# DSP_GPIO_Digital.net
KiCad netlist of a schematic drawn in Altium Designer
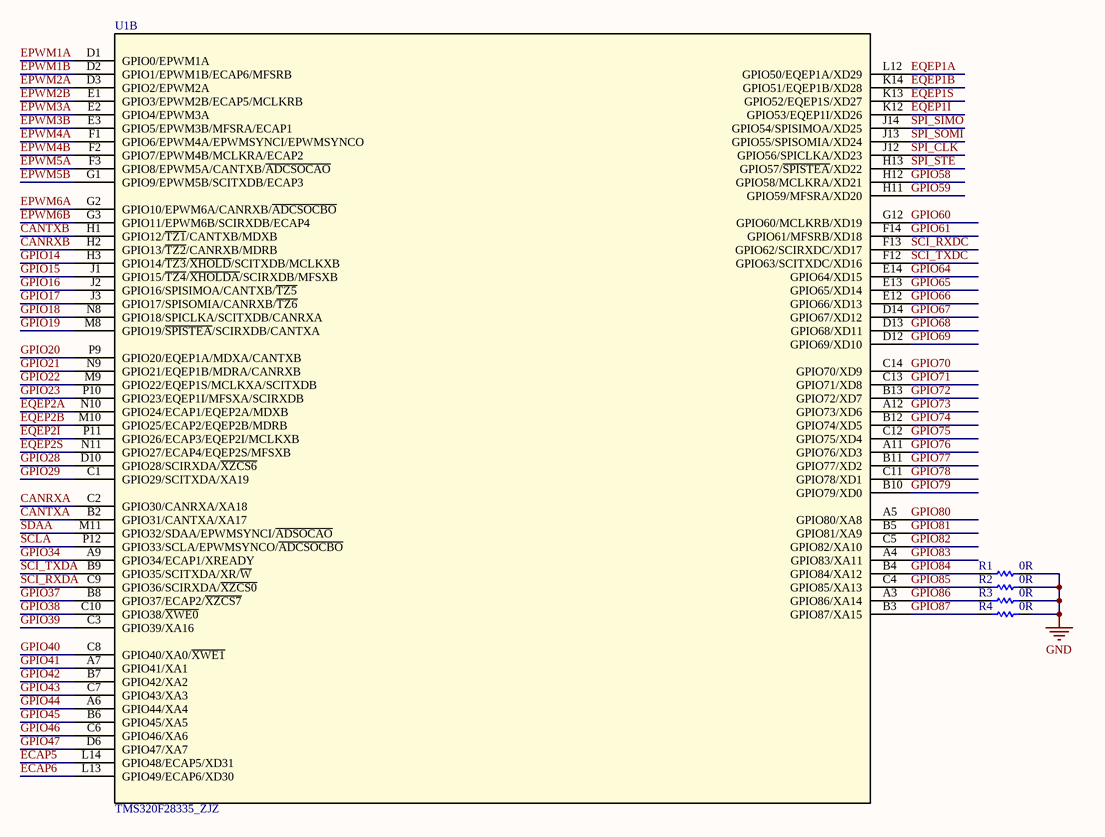
[diagram p0: DSP_GPIO&Digital.SchDoc]

(export (version "E")
  (design (tool "Eeschema 10.0.6"))
  (components
    (comp (ref "R1")
      (value "0R")
      (footprint "r0603")
      (description "Resistor")
      (fields (field (name "Comment") "Res1") (field (name "PUBLISHER") "Altium Limited"))
      (libsource (lib "Miscellaneous Devices") (part "Res1"))
    )
    (comp (ref "R2")
      (value "0R")
      (footprint "r0603")
      (description "Resistor")
      (fields (field (name "Comment") "Res1") (field (name "PUBLISHER") "Altium Limited"))
      (libsource (lib "Miscellaneous Devices") (part "Res1"))
    )
    (comp (ref "R3")
      (value "0R")
      (footprint "r0603")
      (description "Resistor")
      (fields (field (name "Comment") "Res1") (field (name "PUBLISHER") "Altium Limited"))
      (libsource (lib "Miscellaneous Devices") (part "Res1"))
    )
    (comp (ref "R4")
      (value "0R")
      (footprint "r0603")
      (description "Resistor")
      (fields (field (name "Comment") "Res1") (field (name "PUBLISHER") "Altium Limited"))
      (libsource (lib "Miscellaneous Devices") (part "Res1"))
    )
    (comp (ref "U1")
      (value "TMS320F28335_ZJZ")
      (footprint "ZJZ176")
      (description "Imported")
      (fields
        (field (name "MANUFACTURER") "Texas Instruments")
        (field (name "GENERIC_PART_NUMBER") "TMS320F28335")
      )
      (libsource (lib "schlib_by_wjy") (part "TMS320F28335_ZJZ"))
    )
  )
  (nets
    (net (code "1") (name "/CANRXA") (class "Default")
      (node (ref "U1") (pin "C2") (pinfunction "GPIO30/CANRXA/XA18_C2") (pintype "passive"))
    )
    (net (code "2") (name "/CANRXB") (class "Default")
      (node (ref "U1") (pin "H2") (pinfunction "GPIO13/~{TZ2}/CANRXB/MDRB_H2") (pintype "passive"))
    )
    (net (code "3") (name "/CANTXA") (class "Default")
      (node (ref "U1") (pin "B2") (pinfunction "GPIO31/CANTXA/XA17_B2") (pintype "passive"))
    )
    (net (code "4") (name "/CANTXB") (class "Default")
      (node (ref "U1") (pin "H1") (pinfunction "GPIO12/~{TZ1}/CANTXB/MDXB_H1") (pintype "passive"))
    )
    (net (code "5") (name "/ECAP5") (class "Default")
      (node (ref "U1") (pin "L14") (pinfunction "GPIO48/ECAP5/XD31_L14") (pintype "passive"))
    )
    (net (code "6") (name "/ECAP6") (class "Default")
      (node (ref "U1") (pin "L13") (pinfunction "GPIO49/ECAP6/XD30_L13") (pintype "passive"))
    )
    (net (code "7") (name "/EPWM1A") (class "Default")
      (node (ref "U1") (pin "D1") (pinfunction "GPIO0/EPWM1A_D1") (pintype "passive"))
    )
    (net (code "8") (name "/EPWM1B") (class "Default")
      (node (ref "U1") (pin "D2") (pinfunction "GPIO1/EPWM1B/ECAP6/MFSRB_D2") (pintype "passive"))
    )
    (net (code "9") (name "/EPWM2A") (class "Default")
      (node (ref "U1") (pin "D3") (pinfunction "GPIO2/EPWM2A_D3") (pintype "passive"))
    )
    (net (code "10") (name "/EPWM2B") (class "Default")
      (node (ref "U1") (pin "E1") (pinfunction "GPIO3/EPWM2B/ECAP5/MCLKRB_E1") (pintype "passive"))
    )
    (net (code "11") (name "/EPWM3A") (class "Default")
      (node (ref "U1") (pin "E2") (pinfunction "GPIO4/EPWM3A_E2") (pintype "passive"))
    )
    (net (code "12") (name "/EPWM3B") (class "Default")
      (node (ref "U1") (pin "E3") (pinfunction "GPIO5/EPWM3B/MFSRA/ECAP1_E3") (pintype "passive"))
    )
    (net (code "13") (name "/EPWM4A") (class "Default")
      (node (ref "U1") (pin "F1") (pinfunction "GPIO6/EPWM4A/EPWMSYNCI/EPWMSYNCO_F1") (pintype "passive"))
    )
    (net (code "14") (name "/EPWM4B") (class "Default")
      (node (ref "U1") (pin "F2") (pinfunction "GPIO7/EPWM4B/MCLKRA/ECAP2_F2") (pintype "passive"))
    )
    (net (code "15") (name "/EPWM5A") (class "Default")
      (node (ref "U1") (pin "F3") (pinfunction "GPIO8/EPWM5A/CANTXB/~{ADCSOCAO}_F3") (pintype "passive"))
    )
    (net (code "16") (name "/EPWM5B") (class "Default")
      (node (ref "U1") (pin "G1") (pinfunction "GPIO9/EPWM5B/SCITXDB/ECAP3_G1") (pintype "passive"))
    )
    (net (code "17") (name "/EPWM6A") (class "Default")
      (node (ref "U1") (pin "G2") (pinfunction "GPIO10/EPWM6A/CANRXB/~{ADCSOCBO}_G2") (pintype "passive"))
    )
    (net (code "18") (name "/EPWM6B") (class "Default")
      (node (ref "U1") (pin "G3") (pinfunction "GPIO11/EPWM6B/SCIRXDB/ECAP4_G3") (pintype "passive"))
    )
    (net (code "19") (name "/EQEP1A") (class "Default")
      (node (ref "U1") (pin "L12") (pinfunction "GPIO50/EQEP1A/XD29_L12") (pintype "passive"))
    )
    (net (code "20") (name "/EQEP1B") (class "Default")
      (node (ref "U1") (pin "K14") (pinfunction "GPIO51/EQEP1B/XD28_K14") (pintype "passive"))
    )
    (net (code "21") (name "/EQEP1I") (class "Default")
      (node (ref "U1") (pin "K12") (pinfunction "GPIO53/EQEP1I/XD26_K12") (pintype "passive"))
    )
    (net (code "22") (name "/EQEP1S") (class "Default")
      (node (ref "U1") (pin "K13") (pinfunction "GPIO52/EQEP1S/XD27_K13") (pintype "passive"))
    )
    (net (code "23") (name "/EQEP2A") (class "Default")
      (node (ref "U1") (pin "N10") (pinfunction "GPIO24/ECAP1/EQEP2A/MDXB_N10") (pintype "passive"))
    )
    (net (code "24") (name "/EQEP2B") (class "Default")
      (node (ref "U1") (pin "M10") (pinfunction "GPIO25/ECAP2/EQEP2B/MDRB_M10") (pintype "passive"))
    )
    (net (code "25") (name "/EQEP2I") (class "Default")
      (node (ref "U1") (pin "P11") (pinfunction "GPIO26/ECAP3/EQEP2I/MCLKXB_P11") (pintype "passive"))
    )
    (net (code "26") (name "/EQEP2S") (class "Default")
      (node (ref "U1") (pin "N11") (pinfunction "GPIO27/ECAP4/EQEP2S/MFSXB_N11") (pintype "passive"))
    )
    (net (code "27") (name "/GPIO14") (class "Default")
      (node (ref "U1") (pin "H3") (pinfunction "GPIO14/~{TZ3}/~{XHOLD}/SCITXDB/MCLKXB_H3") (pintype "passive"))
    )
    (net (code "28") (name "/GPIO15") (class "Default")
      (node (ref "U1") (pin "J1") (pinfunction "GPIO15/~{TZ4}/~{XHOLDA}/SCIRXDB/MFSXB_J1") (pintype "passive"))
    )
    (net (code "29") (name "/GPIO16") (class "Default")
      (node (ref "U1") (pin "J2") (pinfunction "GPIO16/SPISIMOA/CANTXB/~{TZ5}_J2") (pintype "passive"))
    )
    (net (code "30") (name "/GPIO17") (class "Default")
      (node (ref "U1") (pin "J3") (pinfunction "GPIO17/SPISOMIA/CANRXB/~{TZ6}_J3") (pintype "passive"))
    )
    (net (code "31") (name "/GPIO18") (class "Default")
      (node (ref "U1") (pin "N8") (pinfunction "GPIO18/SPICLKA/SCITXDB/CANRXA_N8") (pintype "passive"))
    )
    (net (code "32") (name "/GPIO19") (class "Default")
      (node (ref "U1") (pin "M8") (pinfunction "GPIO19/~{SPISTEA}/SCIRXDB/CANTXA_M8") (pintype "passive"))
    )
    (net (code "33") (name "/GPIO20") (class "Default")
      (node (ref "U1") (pin "P9") (pinfunction "GPIO20/EQEP1A/MDXA/CANTXB_P9") (pintype "passive"))
    )
    (net (code "34") (name "/GPIO21") (class "Default")
      (node (ref "U1") (pin "N9") (pinfunction "GPIO21/EQEP1B/MDRA/CANRXB_N9") (pintype "passive"))
    )
    (net (code "35") (name "/GPIO22") (class "Default")
      (node (ref "U1") (pin "M9") (pinfunction "GPIO22/EQEP1S/MCLKXA/SCITXDB_M9") (pintype "passive"))
    )
    (net (code "36") (name "/GPIO23") (class "Default")
      (node (ref "U1") (pin "P10") (pinfunction "GPIO23/EQEP1I/MFSXA/SCIRXDB_P10") (pintype "passive"))
    )
    (net (code "37") (name "/GPIO28") (class "Default")
      (node (ref "U1") (pin "D10") (pinfunction "GPIO28/SCIRXDA/~{XZCS6}_D10") (pintype "passive"))
    )
    (net (code "38") (name "/GPIO29") (class "Default")
      (node (ref "U1") (pin "C1") (pinfunction "GPIO29/SCITXDA/XA19_C1") (pintype "passive"))
    )
    (net (code "39") (name "/GPIO34") (class "Default")
      (node (ref "U1") (pin "A9") (pinfunction "GPIO34/ECAP1/XREADY_A9") (pintype "passive"))
    )
    (net (code "40") (name "/GPIO37") (class "Default")
      (node (ref "U1") (pin "B8") (pinfunction "GPIO37/ECAP2/~{XZCS7}_B8") (pintype "passive"))
    )
    (net (code "41") (name "/GPIO38") (class "Default")
      (node (ref "U1") (pin "C10") (pinfunction "GPIO38/~{XWE0}_C10") (pintype "passive"))
    )
    (net (code "42") (name "/GPIO39") (class "Default")
      (node (ref "U1") (pin "C3") (pinfunction "GPIO39/XA16_C3") (pintype "passive"))
    )
    (net (code "43") (name "/GPIO40") (class "Default")
      (node (ref "U1") (pin "C8") (pinfunction "GPIO40/XA0/~{XWE1}_C8") (pintype "passive"))
    )
    (net (code "44") (name "/GPIO41") (class "Default")
      (node (ref "U1") (pin "A7") (pinfunction "GPIO41/XA1_A7") (pintype "passive"))
    )
    (net (code "45") (name "/GPIO42") (class "Default")
      (node (ref "U1") (pin "B7") (pinfunction "GPIO42/XA2_B7") (pintype "passive"))
    )
    (net (code "46") (name "/GPIO43") (class "Default")
      (node (ref "U1") (pin "C7") (pinfunction "GPIO43/XA3_C7") (pintype "passive"))
    )
    (net (code "47") (name "/GPIO44") (class "Default")
      (node (ref "U1") (pin "A6") (pinfunction "GPIO44/XA4_A6") (pintype "passive"))
    )
    (net (code "48") (name "/GPIO45") (class "Default")
      (node (ref "U1") (pin "B6") (pinfunction "GPIO45/XA5_B6") (pintype "passive"))
    )
    (net (code "49") (name "/GPIO46") (class "Default")
      (node (ref "U1") (pin "C6") (pinfunction "GPIO46/XA6_C6") (pintype "passive"))
    )
    (net (code "50") (name "/GPIO47") (class "Default")
      (node (ref "U1") (pin "D6") (pinfunction "GPIO47/XA7_D6") (pintype "passive"))
    )
    (net (code "51") (name "/GPIO58") (class "Default")
      (node (ref "U1") (pin "H12") (pinfunction "GPIO58/MCLKRA/XD21_H12") (pintype "passive"))
    )
    (net (code "52") (name "/GPIO59") (class "Default")
      (node (ref "U1") (pin "H11") (pinfunction "GPIO59/MFSRA/XD20_H11") (pintype "passive"))
    )
    (net (code "53") (name "/GPIO60") (class "Default")
      (node (ref "U1") (pin "G12") (pinfunction "GPIO60/MCLKRB/XD19_G12") (pintype "passive"))
    )
    (net (code "54") (name "/GPIO61") (class "Default")
      (node (ref "U1") (pin "F14") (pinfunction "GPIO61/MFSRB/XD18_F14") (pintype "passive"))
    )
    (net (code "55") (name "/GPIO64") (class "Default")
      (node (ref "U1") (pin "E14") (pinfunction "GPIO64/XD15_E14") (pintype "passive"))
    )
    (net (code "56") (name "/GPIO65") (class "Default")
      (node (ref "U1") (pin "E13") (pinfunction "GPIO65/XD14_E13") (pintype "passive"))
    )
    (net (code "57") (name "/GPIO66") (class "Default")
      (node (ref "U1") (pin "E12") (pinfunction "GPIO66/XD13_E12") (pintype "passive"))
    )
    (net (code "58") (name "/GPIO67") (class "Default")
      (node (ref "U1") (pin "D14") (pinfunction "GPIO67/XD12_D14") (pintype "passive"))
    )
    (net (code "59") (name "/GPIO68") (class "Default")
      (node (ref "U1") (pin "D13") (pinfunction "GPIO68/XD11_D13") (pintype "passive"))
    )
    (net (code "60") (name "/GPIO69") (class "Default")
      (node (ref "U1") (pin "D12") (pinfunction "GPIO69/XD10_D12") (pintype "passive"))
    )
    (net (code "61") (name "/GPIO70") (class "Default")
      (node (ref "U1") (pin "C14") (pinfunction "GPIO70/XD9_C14") (pintype "passive"))
    )
    (net (code "62") (name "/GPIO71") (class "Default")
      (node (ref "U1") (pin "C13") (pinfunction "GPIO71/XD8_C13") (pintype "passive"))
    )
    (net (code "63") (name "/GPIO72") (class "Default")
      (node (ref "U1") (pin "B13") (pinfunction "GPIO72/XD7_B13") (pintype "passive"))
    )
    (net (code "64") (name "/GPIO73") (class "Default")
      (node (ref "U1") (pin "A12") (pinfunction "GPIO73/XD6_A12") (pintype "passive"))
    )
    (net (code "65") (name "/GPIO74") (class "Default")
      (node (ref "U1") (pin "B12") (pinfunction "GPIO74/XD5_B12") (pintype "passive"))
    )
    (net (code "66") (name "/GPIO75") (class "Default")
      (node (ref "U1") (pin "C12") (pinfunction "GPIO75/XD4_C12") (pintype "passive"))
    )
    (net (code "67") (name "/GPIO76") (class "Default")
      (node (ref "U1") (pin "A11") (pinfunction "GPIO76/XD3_A11") (pintype "passive"))
    )
    (net (code "68") (name "/GPIO77") (class "Default")
      (node (ref "U1") (pin "B11") (pinfunction "GPIO77/XD2_B11") (pintype "passive"))
    )
    (net (code "69") (name "/GPIO78") (class "Default")
      (node (ref "U1") (pin "C11") (pinfunction "GPIO78/XD1_C11") (pintype "passive"))
    )
    (net (code "70") (name "/GPIO79") (class "Default")
      (node (ref "U1") (pin "B10") (pinfunction "GPIO79/XD0_B10") (pintype "passive"))
    )
    (net (code "71") (name "/GPIO80") (class "Default")
      (node (ref "U1") (pin "A5") (pinfunction "GPIO80/XA8_A5") (pintype "passive"))
    )
    (net (code "72") (name "/GPIO81") (class "Default")
      (node (ref "U1") (pin "B5") (pinfunction "GPIO81/XA9_B5") (pintype "passive"))
    )
    (net (code "73") (name "/GPIO82") (class "Default")
      (node (ref "U1") (pin "C5") (pinfunction "GPIO82/XA10_C5") (pintype "passive"))
    )
    (net (code "74") (name "/GPIO83") (class "Default")
      (node (ref "U1") (pin "A4") (pinfunction "GPIO83/XA11_A4") (pintype "passive"))
    )
    (net (code "75") (name "/GPIO84") (class "Default")
      (node (ref "R1") (pin "2") (pinfunction "2_2") (pintype "passive"))
      (node (ref "U1") (pin "B4") (pinfunction "GPIO84/XA12_B4") (pintype "passive"))
    )
    (net (code "76") (name "/GPIO85") (class "Default")
      (node (ref "R2") (pin "2") (pinfunction "2_2") (pintype "passive"))
      (node (ref "U1") (pin "C4") (pinfunction "GPIO85/XA13_C4") (pintype "passive"))
    )
    (net (code "77") (name "/GPIO86") (class "Default")
      (node (ref "R3") (pin "2") (pinfunction "2_2") (pintype "passive"))
      (node (ref "U1") (pin "A3") (pinfunction "GPIO86/XA14_A3") (pintype "passive"))
    )
    (net (code "78") (name "/GPIO87") (class "Default")
      (node (ref "R4") (pin "2") (pinfunction "2_2") (pintype "passive"))
      (node (ref "U1") (pin "B3") (pinfunction "GPIO87/XA15_B3") (pintype "passive"))
    )
    (net (code "79") (name "/SCI_RXDA") (class "Default")
      (node (ref "U1") (pin "C9") (pinfunction "GPIO36/SCIRXDA/~{XZCS0}_C9") (pintype "passive"))
    )
    (net (code "80") (name "/SCI_RXDC") (class "Default")
      (node (ref "U1") (pin "F13") (pinfunction "GPIO62/SCIRXDC/XD17_F13") (pintype "passive"))
    )
    (net (code "81") (name "/SCI_TXDA") (class "Default")
      (node (ref "U1") (pin "B9") (pinfunction "GPIO35/SCITXDA/XR/~{W}_B9") (pintype "passive"))
    )
    (net (code "82") (name "/SCI_TXDC") (class "Default")
      (node (ref "U1") (pin "F12") (pinfunction "GPIO63/SCITXDC/XD16_F12") (pintype "passive"))
    )
    (net (code "83") (name "/SCLA") (class "Default")
      (node (ref "U1") (pin "P12") (pinfunction "GPIO33/SCLA/EPWMSYNCO/~{ADCSOCBO}_P12") (pintype "passive"))
    )
    (net (code "84") (name "/SDAA") (class "Default")
      (node (ref "U1") (pin "M11") (pinfunction "GPIO32/SDAA/EPWMSYNCI/~{ADSOCAO}_M11") (pintype "passive"))
    )
    (net (code "85") (name "/SPI_CLK") (class "Default")
      (node (ref "U1") (pin "J12") (pinfunction "GPIO56/SPICLKA/XD23_J12") (pintype "passive"))
    )
    (net (code "86") (name "/SPI_SIMO") (class "Default")
      (node (ref "U1") (pin "J14") (pinfunction "GPIO54/SPISIMOA/XD25_J14") (pintype "passive"))
    )
    (net (code "87") (name "/SPI_SOMI") (class "Default")
      (node (ref "U1") (pin "J13") (pinfunction "GPIO55/SPISOMIA/XD24_J13") (pintype "passive"))
    )
    (net (code "88") (name "/SPI_STE") (class "Default")
      (node (ref "U1") (pin "H13") (pinfunction "GPIO57/~{SPISTEA}/XD22_H13") (pintype "passive"))
    )
    (net (code "89") (name "GND") (class "Default")
      (node (ref "R1") (pin "1") (pinfunction "1_1") (pintype "passive"))
      (node (ref "R2") (pin "1") (pinfunction "1_1") (pintype "passive"))
      (node (ref "R3") (pin "1") (pinfunction "1_1") (pintype "passive"))
      (node (ref "R4") (pin "1") (pinfunction "1_1") (pintype "passive"))
    )
  )
)
